# SCH_SQRT_2022-07-01.net
KiCad netlist of a schematic drawn in EasyEDA
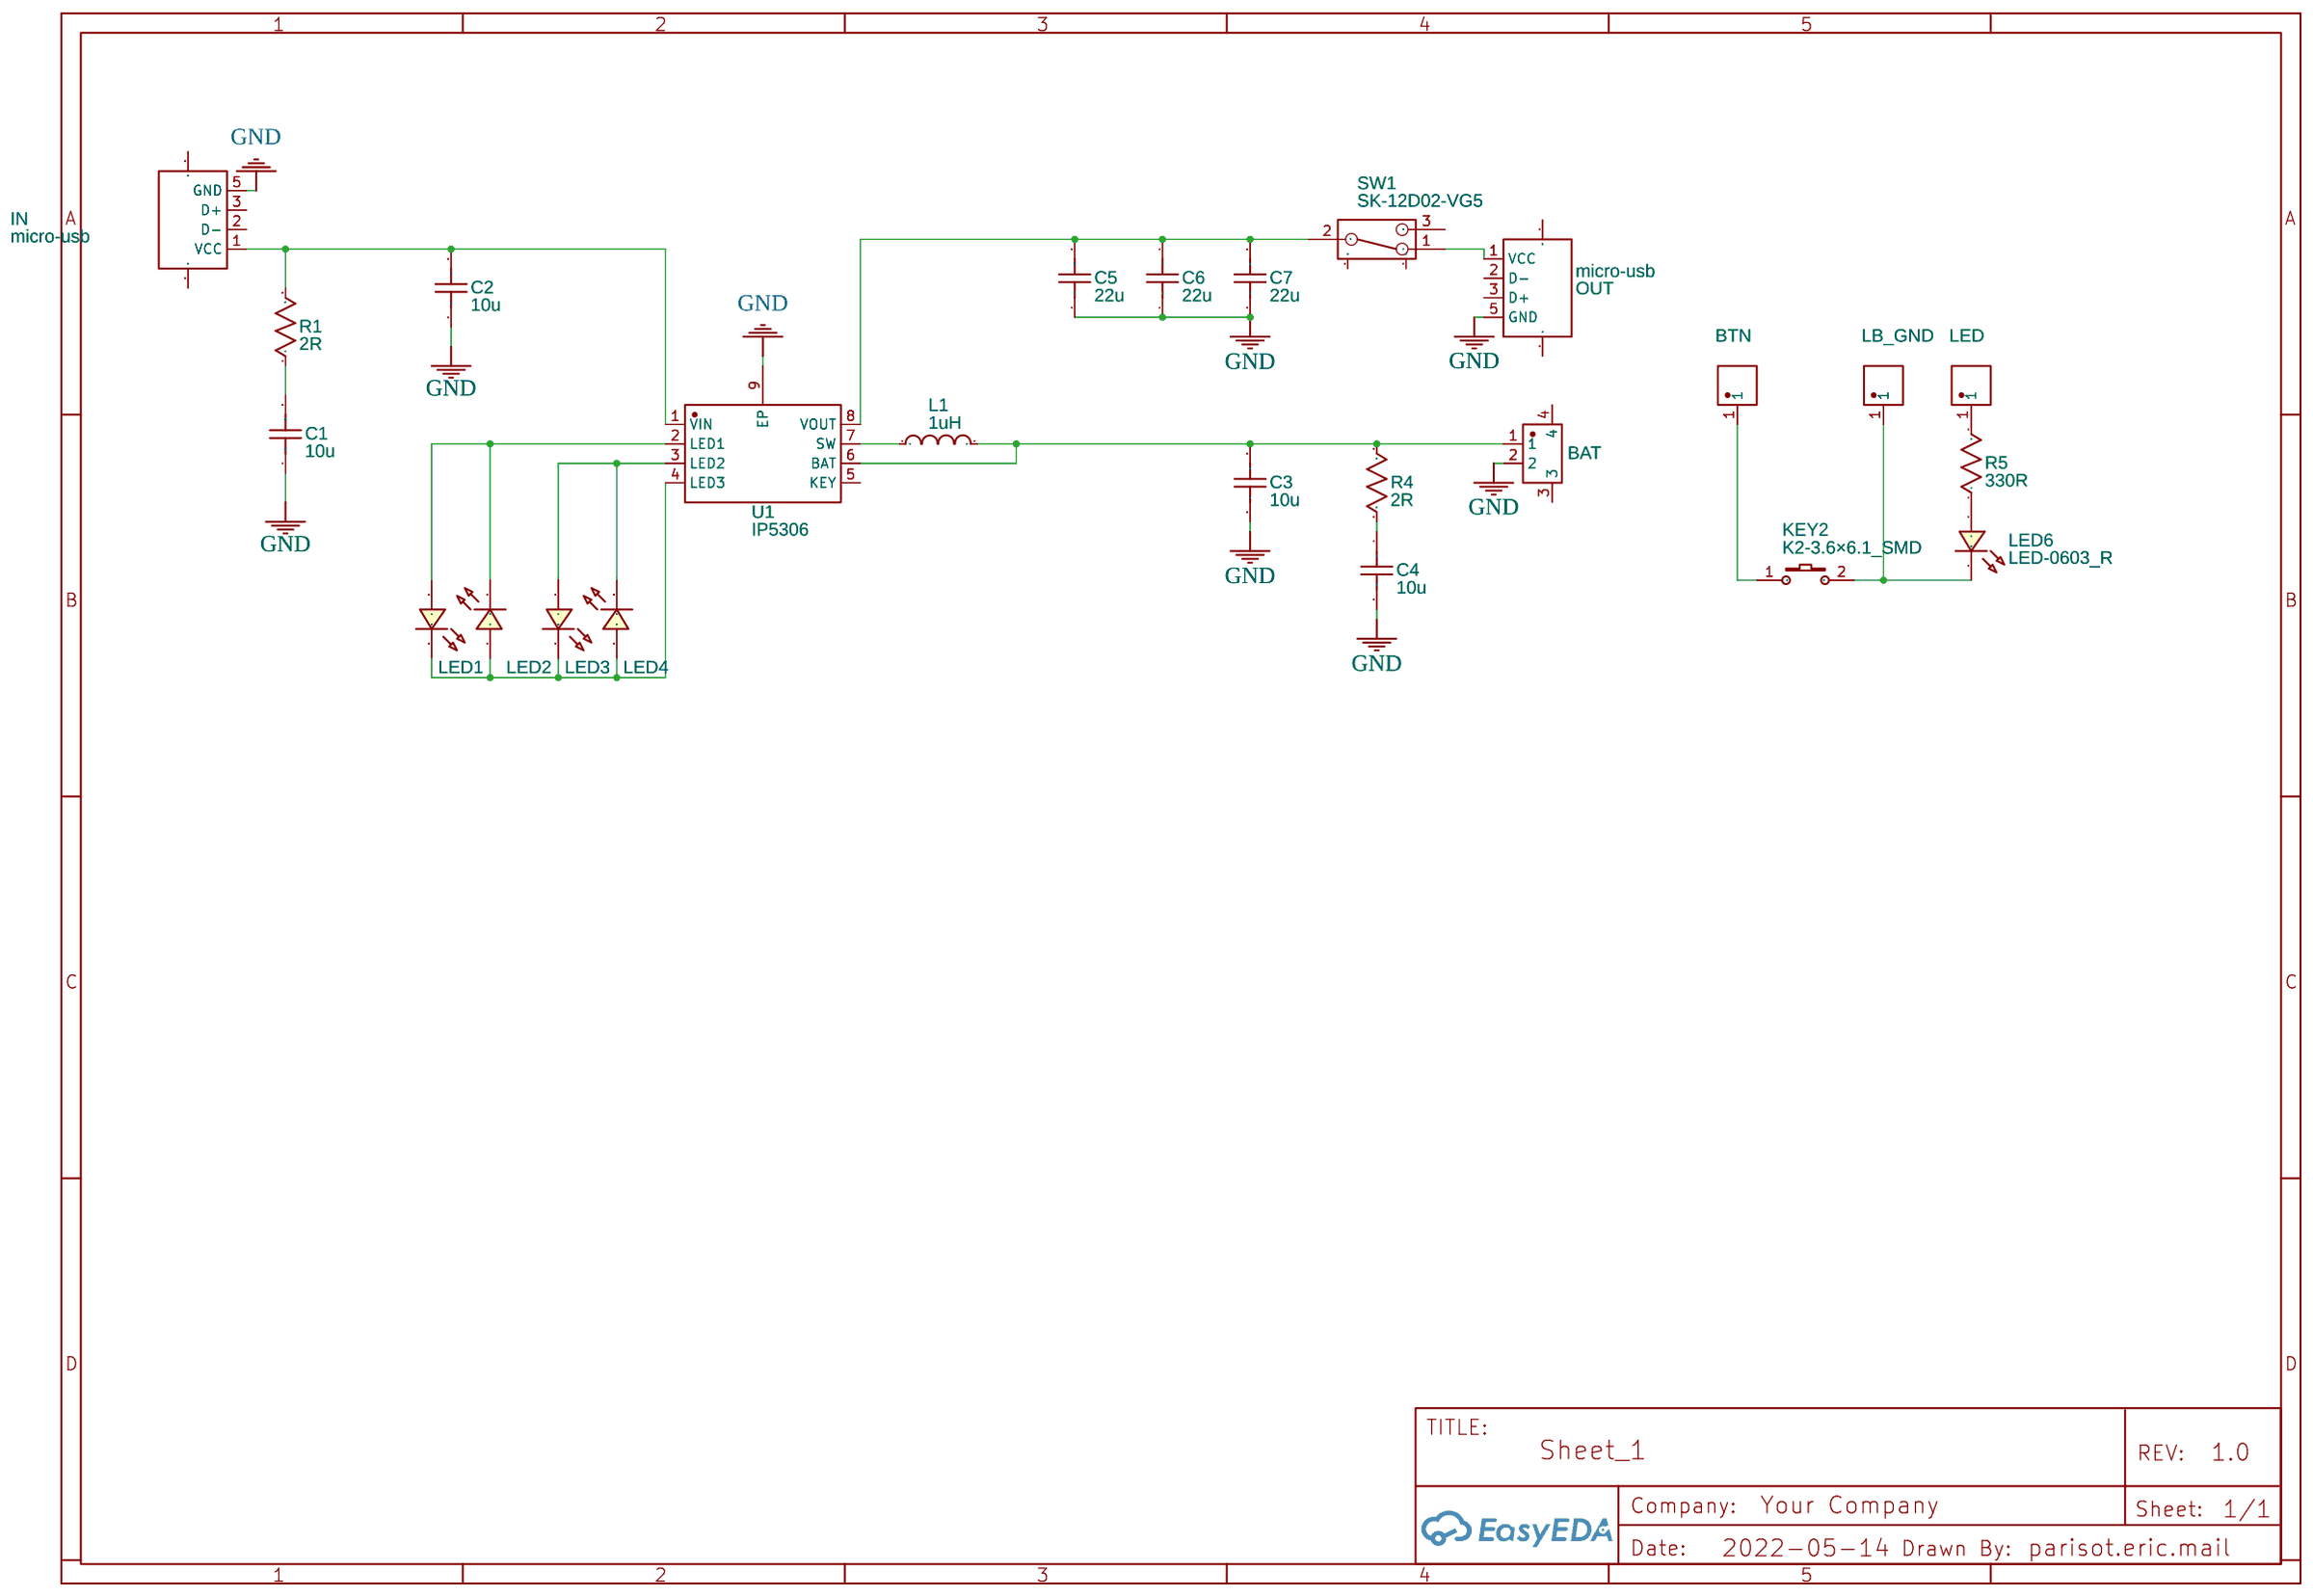
[diagram p0: schematic sheet]

(export (version "E")
  (design (tool "Eeschema 10.0.6"))
  (components
    (comp (ref "BAT")
      (value "PH2.0-2PWB")
      (fields
        (field (name "BOM_Manufacturer Part") "PH2.0-2PWB Horizontal")
        (field (name "BOM_Supplier Part") "C47647")
      )
      (libsource (lib "") (part "PH2.0-2PWB"))
    )
    (comp (ref "BTN")
      (value "BAT")
      (fields
        (field (name "BOM_Manufacturer Part") "pogopin 弹簧顶针(9.0H-2.0T直通加粗)")
        (field (name "BOM_Supplier Part") "C9900001338")
      )
      (libsource (lib "") (part "POGOPIN 弹簧顶针(9.0H-2.0T直通加粗)_2"))
    )
    (comp (ref "C1") (value "10u") (libsource (lib "") (part "C_0603_US")))
    (comp (ref "C2") (value "10u") (libsource (lib "") (part "C_0603_US")))
    (comp (ref "C3") (value "10u") (libsource (lib "") (part "C_0603_US")))
    (comp (ref "C4") (value "10u") (libsource (lib "") (part "C_0603_US_1")))
    (comp (ref "C5") (value "22u") (libsource (lib "") (part "C_0603_US")))
    (comp (ref "C6") (value "22u") (libsource (lib "") (part "C_0603_US")))
    (comp (ref "C7") (value "22u") (libsource (lib "") (part "C_0603_US")))
    (comp (ref "IN")
      (value "micro-usb")
      (fields (field (name "BOM_Manufacturer Part") "USB-05") (field (name "BOM_Supplier Part") "C112454"))
      (libsource (lib "") (part "USB-Type A_Male"))
    )
    (comp (ref "KEY2")
      (value "K2-3.6×6.1_SMD")
      (fields
        (field (name "BOM_Manufacturer Part") "K2-1107ST-A4SW-06")
        (field (name "BOM_Supplier Part") "C118141")
      )
      (libsource (lib "") (part "K2-3.6×6.1_SMD"))
    )
    (comp (ref "L1") (value "1uH") (libsource (lib "") (part "L0603_US")))
    (comp (ref "LB_GND")
      (value "BAT")
      (fields
        (field (name "BOM_Manufacturer Part") "pogopin 弹簧顶针(9.0H-2.0T直通加粗)")
        (field (name "BOM_Supplier Part") "C9900001338")
      )
      (libsource (lib "") (part "POGOPIN 弹簧顶针(9.0H-2.0T直通加粗)_1"))
    )
    (comp (ref "LED")
      (value "BAT")
      (fields
        (field (name "BOM_Manufacturer Part") "pogopin 弹簧顶针(9.0H-2.0T直通加粗)")
        (field (name "BOM_Supplier Part") "C9900001338")
      )
      (libsource (lib "") (part "POGOPIN 弹簧顶针(9.0H-2.0T直通加粗)"))
    )
    (comp (ref "LED1")
      (value "LED-0603_R")
      (fields
        (field (name "BOM_Manufacturer Part") "19-217/R6C-AL1M2VY/3T")
        (field (name "BOM_Supplier Part") "C72044")
      )
      (libsource (lib "") (part "LED-0603_R"))
    )
    (comp (ref "LED2")
      (value "LED-0603_R")
      (fields
        (field (name "BOM_Manufacturer Part") "19-217/R6C-AL1M2VY/3T")
        (field (name "BOM_Supplier Part") "C72044")
      )
      (libsource (lib "") (part "LED-0603_R_1"))
    )
    (comp (ref "LED3")
      (value "LED-0603_R")
      (fields
        (field (name "BOM_Manufacturer Part") "19-217/R6C-AL1M2VY/3T")
        (field (name "BOM_Supplier Part") "C72044")
      )
      (libsource (lib "") (part "LED-0603_R"))
    )
    (comp (ref "LED4")
      (value "LED-0603_R")
      (fields
        (field (name "BOM_Manufacturer Part") "19-217/R6C-AL1M2VY/3T")
        (field (name "BOM_Supplier Part") "C72044")
      )
      (libsource (lib "") (part "LED-0603_R_1"))
    )
    (comp (ref "LED6")
      (value "LED-0603_R")
      (fields
        (field (name "BOM_Manufacturer Part") "19-217/R6C-AL1M2VY/3T")
        (field (name "BOM_Supplier Part") "C72044")
      )
      (libsource (lib "") (part "LED-0603_R"))
    )
    (comp (ref "OUT")
      (value "micro-usb")
      (fields (field (name "BOM_Manufacturer Part") "USB-05") (field (name "BOM_Supplier Part") "C112454"))
      (libsource (lib "") (part "USB-Type A_Male_1"))
    )
    (comp (ref "R1") (value "2R") (libsource (lib "") (part "R_0603_US")))
    (comp (ref "R4") (value "2R") (libsource (lib "") (part "R_0603_US")))
    (comp (ref "R5") (value "330R") (libsource (lib "") (part "R_0603_US")))
    (comp (ref "SW1")
      (value "SK-12D02-VG5")
      (fields (field (name "BOM_Supplier Part") "C480340"))
      (libsource (lib "") (part "SK-12D02-VG5"))
    )
    (comp (ref "U1")
      (value "IP5306")
      (fields (field (name "BOM_Supplier Part") "C181692"))
      (libsource (lib "") (part "IP5306"))
    )
  )
  (nets
    (net (code "1") (name "GND") (class "Default")
      (node (ref "BAT") (pin "2") (pinfunction "2_2") (pintype "unspecified"))
      (node (ref "C1") (pin "1") (pinfunction "1_1") (pintype "unspecified"))
      (node (ref "C2") (pin "1") (pinfunction "1_1") (pintype "unspecified"))
      (node (ref "C3") (pin "1") (pinfunction "1_1") (pintype "unspecified"))
      (node (ref "C4") (pin "2") (pinfunction "2_2") (pintype "unspecified"))
      (node (ref "C5") (pin "1") (pinfunction "1_1") (pintype "unspecified"))
      (node (ref "C6") (pin "1") (pinfunction "1_1") (pintype "unspecified"))
      (node (ref "C7") (pin "1") (pinfunction "1_1") (pintype "unspecified"))
      (node (ref "IN") (pin "5") (pinfunction "GND_5") (pintype "input"))
      (node (ref "OUT") (pin "5") (pinfunction "GND_5") (pintype "input"))
      (node (ref "U1") (pin "9") (pinfunction "EP_9") (pintype "unspecified"))
    )
    (net (code "2") (name "Net-(BTN-Pad1)") (class "Default")
      (node (ref "BTN") (pin "1") (pinfunction "1_1") (pintype "unspecified"))
      (node (ref "KEY2") (pin "1") (pinfunction "1_1") (pintype "unspecified"))
    )
    (net (code "3") (name "Net-(C1-Pad2)") (class "Default")
      (node (ref "C1") (pin "2") (pinfunction "2_2") (pintype "unspecified"))
      (node (ref "R1") (pin "1") (pinfunction "1_1") (pintype "unspecified"))
    )
    (net (code "4") (name "Net-(C4-Pad1)") (class "Default")
      (node (ref "C4") (pin "1") (pinfunction "1_1") (pintype "unspecified"))
      (node (ref "R4") (pin "1") (pinfunction "1_1") (pintype "unspecified"))
    )
    (net (code "5") (name "Net-(IN-VCC)") (class "Default")
      (node (ref "C2") (pin "2") (pinfunction "2_2") (pintype "unspecified"))
      (node (ref "IN") (pin "1") (pinfunction "VCC_1") (pintype "input"))
      (node (ref "R1") (pin "2") (pinfunction "2_2") (pintype "unspecified"))
      (node (ref "U1") (pin "1") (pinfunction "VIN_1") (pintype "unspecified"))
    )
    (net (code "6") (name "Net-(KEY2-Pad2)") (class "Default")
      (node (ref "KEY2") (pin "2") (pinfunction "2_2") (pintype "unspecified"))
      (node (ref "LB_GND") (pin "1") (pinfunction "1_1") (pintype "unspecified"))
      (node (ref "LED6") (pin "2") (pinfunction "2_2") (pintype "unspecified"))
    )
    (net (code "7") (name "Net-(LED-Pad1)") (class "Default")
      (node (ref "LED") (pin "1") (pinfunction "1_1") (pintype "unspecified"))
      (node (ref "R5") (pin "2") (pinfunction "2_2") (pintype "unspecified"))
    )
    (net (code "8") (name "Net-(LED6-Pad1)") (class "Default")
      (node (ref "LED6") (pin "1") (pinfunction "1_1") (pintype "unspecified"))
      (node (ref "R5") (pin "1") (pinfunction "1_1") (pintype "unspecified"))
    )
    (net (code "9") (name "Net-(OUT-VCC)") (class "Default")
      (node (ref "OUT") (pin "1") (pinfunction "VCC_1") (pintype "input"))
      (node (ref "SW1") (pin "1") (pinfunction "1_1") (pintype "unspecified"))
    )
    (net (code "10") (name "Net-(U1-BAT)") (class "Default")
      (node (ref "BAT") (pin "1") (pinfunction "1_1") (pintype "unspecified"))
      (node (ref "C3") (pin "2") (pinfunction "2_2") (pintype "unspecified"))
      (node (ref "L1") (pin "2") (pinfunction "2_2") (pintype "unspecified"))
      (node (ref "R4") (pin "2") (pinfunction "2_2") (pintype "unspecified"))
      (node (ref "U1") (pin "6") (pinfunction "BAT_6") (pintype "unspecified"))
    )
    (net (code "11") (name "Net-(U1-LED1)") (class "Default")
      (node (ref "LED1") (pin "1") (pinfunction "1_1") (pintype "unspecified"))
      (node (ref "LED2") (pin "2") (pinfunction "2_2") (pintype "unspecified"))
      (node (ref "U1") (pin "2") (pinfunction "LED1_2") (pintype "unspecified"))
    )
    (net (code "12") (name "Net-(U1-LED2)") (class "Default")
      (node (ref "LED3") (pin "1") (pinfunction "1_1") (pintype "unspecified"))
      (node (ref "LED4") (pin "2") (pinfunction "2_2") (pintype "unspecified"))
      (node (ref "U1") (pin "3") (pinfunction "LED2_3") (pintype "unspecified"))
    )
    (net (code "13") (name "Net-(U1-LED3)") (class "Default")
      (node (ref "LED1") (pin "2") (pinfunction "2_2") (pintype "unspecified"))
      (node (ref "LED2") (pin "1") (pinfunction "1_1") (pintype "unspecified"))
      (node (ref "LED3") (pin "2") (pinfunction "2_2") (pintype "unspecified"))
      (node (ref "LED4") (pin "1") (pinfunction "1_1") (pintype "unspecified"))
      (node (ref "U1") (pin "4") (pinfunction "LED3_4") (pintype "unspecified"))
    )
    (net (code "14") (name "Net-(U1-SW)") (class "Default")
      (node (ref "L1") (pin "1") (pinfunction "1_1") (pintype "unspecified"))
      (node (ref "U1") (pin "7") (pinfunction "SW_7") (pintype "unspecified"))
    )
    (net (code "15") (name "Net-(U1-VOUT)") (class "Default")
      (node (ref "C5") (pin "2") (pinfunction "2_2") (pintype "unspecified"))
      (node (ref "C6") (pin "2") (pinfunction "2_2") (pintype "unspecified"))
      (node (ref "C7") (pin "2") (pinfunction "2_2") (pintype "unspecified"))
      (node (ref "SW1") (pin "2") (pinfunction "2_2") (pintype "unspecified"))
      (node (ref "U1") (pin "8") (pinfunction "VOUT_8") (pintype "unspecified"))
    )
    (net (code "16") (name "unconnected-(BAT-Pad3)") (class "Default")
      (node (ref "BAT") (pin "3") (pinfunction "3_3") (pintype "unspecified"))
    )
    (net (code "17") (name "unconnected-(BAT-Pad4)") (class "Default")
      (node (ref "BAT") (pin "4") (pinfunction "4_4") (pintype "unspecified"))
    )
    (net (code "18") (name "unconnected-(IN-5-Pad6)") (class "Default")
      (node (ref "IN") (pin "6") (pinfunction "5_6") (pintype "unspecified"))
    )
    (net (code "19") (name "unconnected-(IN-D+-Pad3)") (class "Default")
      (node (ref "IN") (pin "3") (pinfunction "D+_3") (pintype "input"))
    )
    (net (code "20") (name "unconnected-(IN-D--Pad2)") (class "Default")
      (node (ref "IN") (pin "2") (pinfunction "D-_2") (pintype "input"))
    )
    (net (code "21") (name "unconnected-(IN-Pad6)") (class "Default")
      (node (ref "IN") (pin "6") (pinfunction "6_6") (pintype "unspecified"))
    )
    (net (code "22") (name "unconnected-(OUT-5-Pad6)") (class "Default")
      (node (ref "OUT") (pin "6") (pinfunction "5_6") (pintype "unspecified"))
    )
    (net (code "23") (name "unconnected-(OUT-D+-Pad3)") (class "Default")
      (node (ref "OUT") (pin "3") (pinfunction "D+_3") (pintype "input"))
    )
    (net (code "24") (name "unconnected-(OUT-D--Pad2)") (class "Default")
      (node (ref "OUT") (pin "2") (pinfunction "D-_2") (pintype "input"))
    )
    (net (code "25") (name "unconnected-(OUT-Pad6)") (class "Default")
      (node (ref "OUT") (pin "6") (pinfunction "6_6") (pintype "unspecified"))
    )
    (net (code "26") (name "unconnected-(SW1-Pad3)") (class "Default")
      (node (ref "SW1") (pin "3") (pinfunction "3_3") (pintype "unspecified"))
    )
    (net (code "27") (name "unconnected-(SW1-Pad4)") (class "Default")
      (node (ref "SW1") (pin "4") (pinfunction "4_4") (pintype "unspecified"))
    )
    (net (code "28") (name "unconnected-(SW1-Pad5)") (class "Default")
      (node (ref "SW1") (pin "5") (pinfunction "5_5") (pintype "unspecified"))
    )
    (net (code "29") (name "unconnected-(U1-KEY-Pad5)") (class "Default")
      (node (ref "U1") (pin "5") (pinfunction "KEY_5") (pintype "unspecified"))
    )
  )
)
